# Power.net
KiCad netlist of a schematic drawn in Altium Designer
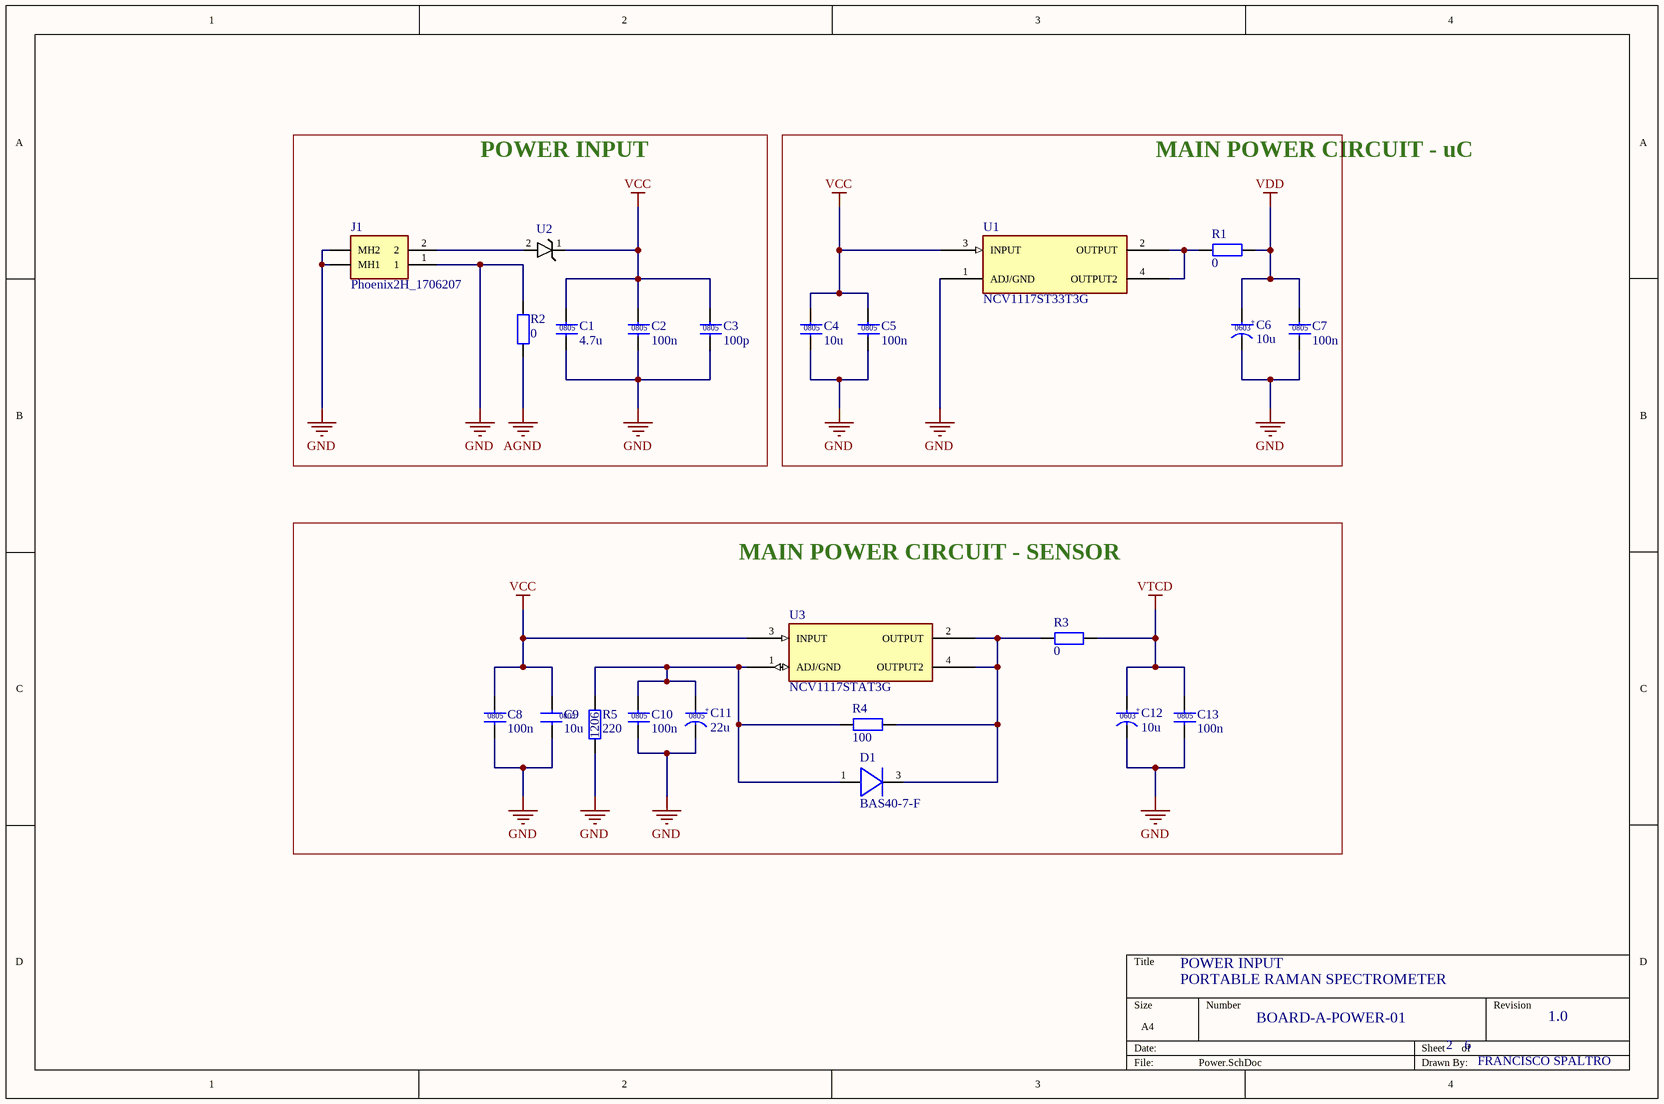
[diagram p0: Power.SchDoc]

(export (version "E")
  (design (tool "Eeschema 10.0.6"))
  (components
    (comp (ref "C1")
      (value "4.7u")
      (footprint "RES_0805")
      (description "Samsung CL21B475KOFNNNE")
      (libsource (lib "Components") (part "CAP_0805"))
    )
    (comp (ref "C2")
      (value "100n")
      (footprint "RES_0805")
      (description "Kemet C0805C104K3RAC7800")
      (libsource (lib "Components") (part "CAP_0805"))
    )
    (comp (ref "C3")
      (value "100p")
      (footprint "RES_0805")
      (description "Kemet C0805C101J5GACTU")
      (libsource (lib "Components") (part "CAP_0805"))
    )
    (comp (ref "C4")
      (value "10u")
      (footprint "RES_0805")
      (description "Samsung CL21B106KOQNNNE")
      (libsource (lib "Components") (part "CAP_0805"))
    )
    (comp (ref "C5")
      (value "100n")
      (footprint "RES_0805")
      (description "Kemet C0805C104K3RAC7800")
      (libsource (lib "Components") (part "CAP_0805"))
    )
    (comp (ref "C6")
      (value "10u")
      (footprint "CAP_0603_POL-M")
      (description "KYOCERA AVX F381A106MMA")
      (libsource (lib "Components") (part "CAP_0603_POL"))
    )
    (comp (ref "C7")
      (value "100n")
      (footprint "RES_0805")
      (description "Kemet C0805C104K3RAC7800")
      (libsource (lib "Components") (part "CAP_0805"))
    )
    (comp (ref "C8")
      (value "100n")
      (footprint "RES_0805")
      (description "Kemet C0805C104K3RAC7800")
      (libsource (lib "Components") (part "CAP_0805"))
    )
    (comp (ref "C9")
      (value "10u")
      (footprint "RES_0805")
      (description "Samsung CL21B106KOQNNNE")
      (libsource (lib "Components") (part "CAP_0805"))
    )
    (comp (ref "C10")
      (value "100n")
      (footprint "RES_0805")
      (description "Kemet C0805C104K3RAC7800")
      (libsource (lib "Components") (part "CAP_0805"))
    )
    (comp (ref "C11")
      (value "22u")
      (footprint "CAP_0805_POL")
      (description "Kyocera AVX F951A226MPAAQ2")
      (libsource (lib "Components") (part "CAP_0805_POL"))
    )
    (comp (ref "C12")
      (value "10u")
      (footprint "CAP_0603_POL-M")
      (description "KYOCERA AVX F381A106MMA")
      (libsource (lib "Components") (part "CAP_0603_POL"))
    )
    (comp (ref "C13")
      (value "100n")
      (footprint "RES_0805")
      (description "Kemet C0805C104K3RAC7800")
      (libsource (lib "Components") (part "CAP_0805"))
    )
    (comp (ref "D1")
      (value "BAS40-7-F")
      (footprint "SOT-23_DIO-M")
      (description "Description")
      (fields (field (name "COPYRIGHT") "Copyright (C) 2025 Ultra Librarian. All rights reserved."))
      (libsource (lib "Components") (part "DIODE-BAS40-7-F"))
    )
    (comp (ref "J1")
      (value "Phoenix2H_1706207")
      (footprint "PHOENIX_1706207")
      (fields (field (name "MP") "1706207"))
      (libsource (lib "Components") (part "Phoenix2H_1706207"))
    )
    (comp (ref "R1")
      (value "0")
      (footprint "RES_0805")
      (description "Generic Capacitor")
      (libsource (lib "Components") (part "RES_0805"))
    )
    (comp (ref "R2")
      (value "0")
      (footprint "RES_0805")
      (description "Generic Capacitor")
      (libsource (lib "Components") (part "RES_0805"))
    )
    (comp (ref "R3")
      (value "0")
      (footprint "RES_0805")
      (description "Generic Capacitor")
      (libsource (lib "Components") (part "RES_0805"))
    )
    (comp (ref "R4")
      (value "100")
      (footprint "RES_0805")
      (description "Generic Capacitor")
      (libsource (lib "Components") (part "RES_0805"))
    )
    (comp (ref "R5")
      (value "220")
      (footprint "RES_1206")
      (description "Generic 1206 Resistor")
      (libsource (lib "Components") (part "RES_1206"))
    )
    (comp (ref "U1")
      (value "NCV1117ST33T3G")
      (footprint "SOT230P700X180-4N")
      (description "Linear Voltage Regulator IC Positive Fixed 1 Output 1A SOT-223")
      (fields (field (name "MF") "ON Semiconductor"))
      (libsource (lib "CI") (part "REG3_3-NCV1117ST33T3G"))
    )
    (comp (ref "U2")
      (value "MBRA340T3G")
      (footprint "SMA_ONS")
      (description "Description")
      (fields (field (name "COPYRIGHT") "Copyright (C) 2025 Ultra Librarian. All rights reserved."))
      (libsource (lib "Components") (part "MBRA340T3G"))
    )
    (comp (ref "U3")
      (value "NCV1117STAT3G")
      (footprint "SOT223-3_ONS-M")
      (description "Description")
      (fields (field (name "COPYRIGHT") "Copyright (C) 2025 Ultra Librarian. All rights reserved."))
      (libsource (lib "Components") (part "NCV1117STAT3G"))
    )
  )
  (nets
    (net (code "1") (name "AGND") (class "Default")
      (node (ref "R2") (pin "1") (pinfunction "1_1") (pintype "passive"))
    )
    (net (code "2") (name "GND") (class "Default")
      (node (ref "C1") (pin "2") (pinfunction "2_2") (pintype "passive"))
      (node (ref "C10") (pin "2") (pinfunction "2_2") (pintype "passive"))
      (node (ref "C11") (pin "2") (pinfunction "2_2") (pintype "passive"))
      (node (ref "C12") (pin "2") (pinfunction "2_2") (pintype "passive"))
      (node (ref "C13") (pin "2") (pinfunction "2_2") (pintype "passive"))
      (node (ref "C2") (pin "2") (pinfunction "2_2") (pintype "passive"))
      (node (ref "C3") (pin "2") (pinfunction "2_2") (pintype "passive"))
      (node (ref "C4") (pin "2") (pinfunction "2_2") (pintype "passive"))
      (node (ref "C5") (pin "2") (pinfunction "2_2") (pintype "passive"))
      (node (ref "C6") (pin "2") (pinfunction "2_2") (pintype "passive"))
      (node (ref "C7") (pin "2") (pinfunction "2_2") (pintype "passive"))
      (node (ref "C8") (pin "2") (pinfunction "2_2") (pintype "passive"))
      (node (ref "C9") (pin "2") (pinfunction "2_2") (pintype "passive"))
      (node (ref "J1") (pin "1") (pinfunction "1_1") (pintype "passive"))
      (node (ref "J1") (pin "MH1") (pinfunction "MH1_MH1") (pintype "passive"))
      (node (ref "J1") (pin "MH2") (pinfunction "MH2_MH2") (pintype "passive"))
      (node (ref "R2") (pin "2") (pinfunction "2_2") (pintype "passive"))
      (node (ref "R5") (pin "1") (pinfunction "1_1") (pintype "passive"))
      (node (ref "U1") (pin "1") (pinfunction "ADJ/GND_1") (pintype "power_in"))
    )
    (net (code "3") (name "Net-(D1-A)") (class "Default")
      (node (ref "C10") (pin "1") (pinfunction "1_1") (pintype "passive"))
      (node (ref "C11") (pin "1") (pinfunction "1_1") (pintype "passive"))
      (node (ref "D1") (pin "1") (pinfunction "A_1") (pintype "passive"))
      (node (ref "R4") (pin "2") (pinfunction "2_2") (pintype "passive"))
      (node (ref "R5") (pin "2") (pinfunction "2_2") (pintype "passive"))
      (node (ref "U3") (pin "1") (pinfunction "ADJ/GND_1") (pintype "bidirectional"))
    )
    (net (code "4") (name "Net-(D1-C)") (class "Default")
      (node (ref "D1") (pin "3") (pinfunction "C_3") (pintype "passive"))
      (node (ref "R3") (pin "1") (pinfunction "1_1") (pintype "passive"))
      (node (ref "R4") (pin "1") (pinfunction "1_1") (pintype "passive"))
      (node (ref "U3") (pin "2") (pinfunction "OUTPUT_2") (pintype "passive"))
      (node (ref "U3") (pin "4") (pinfunction "OUTPUT2_4") (pintype "passive"))
    )
    (net (code "5") (name "Net-(U1-OUTPUT)") (class "Default")
      (node (ref "R1") (pin "1") (pinfunction "1_1") (pintype "passive"))
      (node (ref "U1") (pin "2") (pinfunction "OUTPUT_2") (pintype "passive"))
      (node (ref "U1") (pin "4") (pinfunction "OUTPUT2_4") (pintype "passive"))
    )
    (net (code "6") (name "Net-(U2-ANODE)") (class "Default")
      (node (ref "J1") (pin "2") (pinfunction "2_2") (pintype "power_in"))
      (node (ref "U2") (pin "2") (pinfunction "ANODE_2") (pintype "passive"))
    )
    (net (code "7") (name "VCC") (class "Default")
      (node (ref "C1") (pin "1") (pinfunction "1_1") (pintype "passive"))
      (node (ref "C2") (pin "1") (pinfunction "1_1") (pintype "passive"))
      (node (ref "C3") (pin "1") (pinfunction "1_1") (pintype "passive"))
      (node (ref "C4") (pin "1") (pinfunction "1_1") (pintype "passive"))
      (node (ref "C5") (pin "1") (pinfunction "1_1") (pintype "passive"))
      (node (ref "C8") (pin "1") (pinfunction "1_1") (pintype "passive"))
      (node (ref "C9") (pin "1") (pinfunction "1_1") (pintype "passive"))
      (node (ref "U1") (pin "3") (pinfunction "INPUT_3") (pintype "input"))
      (node (ref "U2") (pin "1") (pinfunction "CATHODE_1") (pintype "passive"))
      (node (ref "U3") (pin "3") (pinfunction "INPUT_3") (pintype "input"))
    )
    (net (code "8") (name "VDD") (class "Default")
      (node (ref "C6") (pin "1") (pinfunction "1_1") (pintype "passive"))
      (node (ref "C7") (pin "1") (pinfunction "1_1") (pintype "passive"))
      (node (ref "R1") (pin "2") (pinfunction "2_2") (pintype "passive"))
    )
    (net (code "9") (name "VTCD") (class "Default")
      (node (ref "C12") (pin "1") (pinfunction "1_1") (pintype "passive"))
      (node (ref "C13") (pin "1") (pinfunction "1_1") (pintype "passive"))
      (node (ref "R3") (pin "2") (pinfunction "2_2") (pintype "passive"))
    )
  )
)
